# spbka.net
KiCad netlist of a schematic drawn in EAGLE
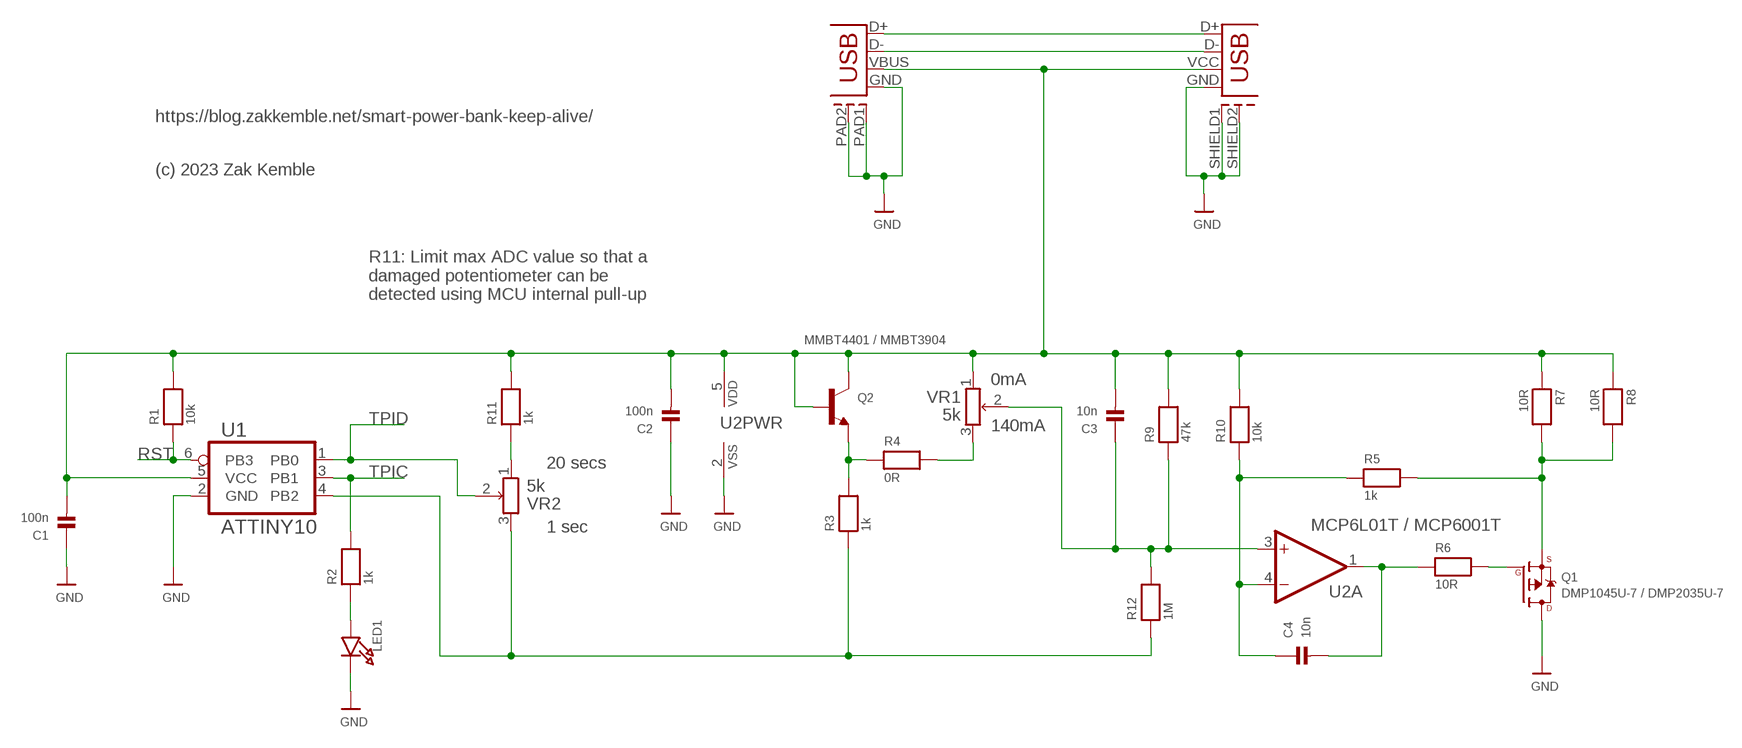
[diagram p0: schematic, sheet 1]

(export (version "E")
  (design (tool "Eeschema 10.0.6"))
  (components
    (comp (ref "C1")
      (value "100n")
      (footprint "eagle-import:0402_XSMALL")
      (libsource (lib "eagle-import") (part "CAP_CERAMIC0402_XSMALL"))
    )
    (comp (ref "C2")
      (value "100n")
      (footprint "eagle-import:0402_XSMALL")
      (libsource (lib "eagle-import") (part "CAP_CERAMIC0402_XSMALL"))
    )
    (comp (ref "C3")
      (value "10n")
      (footprint "eagle-import:0402_XSMALL")
      (libsource (lib "eagle-import") (part "CAP_CERAMIC0402_XSMALL"))
    )
    (comp (ref "C4")
      (value "10n")
      (footprint "eagle-import:0402_XSMALL")
      (libsource (lib "eagle-import") (part "CAP_CERAMIC0402_XSMALL"))
    )
    (comp (ref "LED1")
      (value "LED0603_NOOUTLINE")
      (footprint "eagle-import:CHIPLED_0603_NOOUTLINE")
      (libsource (lib "eagle-import") (part "LED0603_NOOUTLINE"))
    )
    (comp (ref "Q1")
      (value "DMP1045U-7 / DMP2035U-7")
      (footprint "eagle-import:SOT-23-WIDE")
      (libsource (lib "eagle-import") (part "MOSFET-PSOT-23-WIDE"))
    )
    (comp (ref "Q2")
      (value "MMBT4401 / MMBT3904")
      (footprint "eagle-import:SOT23-R")
      (libsource (lib "eagle-import") (part "TRANSISTOR_NPN"))
    )
    (comp (ref "R1")
      (value "10k")
      (footprint "eagle-import:0402_XSMALL")
      (libsource (lib "eagle-import") (part "RESISTOR0402_XSMALL"))
    )
    (comp (ref "R2")
      (value "1k")
      (footprint "eagle-import:0402_XSMALL")
      (libsource (lib "eagle-import") (part "RESISTOR0402_XSMALL"))
    )
    (comp (ref "R3")
      (value "1k")
      (footprint "eagle-import:0402_XSMALL")
      (libsource (lib "eagle-import") (part "RESISTOR0402_XSMALL"))
    )
    (comp (ref "R4")
      (value "0R")
      (footprint "eagle-import:0402_XSMALL")
      (libsource (lib "eagle-import") (part "RESISTOR0402_XSMALL"))
    )
    (comp (ref "R5")
      (value "1k")
      (footprint "eagle-import:0402_XSMALL")
      (libsource (lib "eagle-import") (part "RESISTOR0402_XSMALL"))
    )
    (comp (ref "R6")
      (value "10R")
      (footprint "eagle-import:0402_XSMALL")
      (libsource (lib "eagle-import") (part "RESISTOR0402_XSMALL"))
    )
    (comp (ref "R7")
      (value "10R")
      (footprint "eagle-import:0402_XSMALL")
      (libsource (lib "eagle-import") (part "RESISTOR0402_XSMALL"))
    )
    (comp (ref "R8")
      (value "10R")
      (footprint "eagle-import:0402_XSMALL")
      (libsource (lib "eagle-import") (part "RESISTOR0402_XSMALL"))
    )
    (comp (ref "R9")
      (value "47k")
      (footprint "eagle-import:0402_XSMALL")
      (libsource (lib "eagle-import") (part "RESISTOR0402_XSMALL"))
    )
    (comp (ref "R10")
      (value "10k")
      (footprint "eagle-import:0402_XSMALL")
      (libsource (lib "eagle-import") (part "RESISTOR0402_XSMALL"))
    )
    (comp (ref "R11")
      (value "1k")
      (footprint "eagle-import:0402_XSMALL")
      (libsource (lib "eagle-import") (part "RESISTOR0402_XSMALL"))
    )
    (comp (ref "R12")
      (value "1M")
      (footprint "eagle-import:0402_XSMALL")
      (libsource (lib "eagle-import") (part "RESISTOR0402_XSMALL"))
    )
    (comp (ref "U1")
      (value "ATTINY10")
      (footprint "eagle-import:SOT23-6_SM_PAD")
      (libsource (lib "eagle-import") (part "ATTINY10SM_PAD"))
    )
    (comp (ref "U2")
      (value "MCP6L01T / MCP6001T")
      (footprint "eagle-import:SOT23-5_SM_PAD")
      (libsource (lib "eagle-import") (part "OPAMP_SINGLECONFIG1_SMPAD"))
    )
    (comp (ref "USB1")
      (value "USB-TYPE-AHORZ")
      (footprint "eagle-import:USB-TYPE-A")
      (libsource (lib "eagle-import") (part "USB-TYPE-AHORZ"))
    )
    (comp (ref "USB2")
      (value "USB-PLUG")
      (footprint "eagle-import:USB-TYPE-A-PLUG-SLOT")
      (libsource (lib "eagle-import") (part "USB-PLUG"))
    )
    (comp (ref "VR1")
      (value "5k")
      (footprint "eagle-import:TRIMPOT_BOURNS3MM")
      (libsource (lib "eagle-import") (part "POTENTIOMETERBOURNS3MM"))
    )
    (comp (ref "VR2")
      (value "5k")
      (footprint "eagle-import:TRIMPOT_BOURNS3MM")
      (libsource (lib "eagle-import") (part "POTENTIOMETERBOURNS3MM"))
    )
  )
  (nets
    (net (code "1") (name "/RST") (class "Default")
      (node (ref "R1") (pin "1") (pinfunction "1_1") (pintype "passive"))
      (node (ref "U1") (pin "6") (pinfunction "PB3_6") (pintype "bidirectional"))
    )
    (net (code "2") (name "/TPIC") (class "Default")
      (node (ref "R2") (pin "2") (pinfunction "2_2") (pintype "passive"))
      (node (ref "U1") (pin "3") (pinfunction "PB1_3") (pintype "bidirectional"))
    )
    (net (code "3") (name "/TPID") (class "Default")
      (node (ref "U1") (pin "1") (pinfunction "PB0_1") (pintype "bidirectional"))
      (node (ref "VR2") (pin "2") (pinfunction "1S_2") (pintype "passive"))
    )
    (net (code "4") (name "GND") (class "Default")
      (node (ref "C1") (pin "1") (pinfunction "P$1_1") (pintype "passive"))
      (node (ref "C2") (pin "1") (pinfunction "P$1_1") (pintype "passive"))
      (node (ref "LED1") (pin "C") (pinfunction "C_C") (pintype "passive"))
      (node (ref "Q1") (pin "3") (pinfunction "D_3") (pintype "passive"))
      (node (ref "U1") (pin "2") (pinfunction "GND_2") (pintype "passive"))
      (node (ref "U2") (pin "2") (pinfunction "VSS_2") (pintype "power_in"))
      (node (ref "USB1") (pin "GND") (pinfunction "GND_GND") (pintype "bidirectional"))
      (node (ref "USB1") (pin "SHIELD1") (pinfunction "SHEILD1_SHIELD1") (pintype "bidirectional"))
      (node (ref "USB1") (pin "SHIELD2") (pinfunction "SHEILD2_SHIELD2") (pintype "bidirectional"))
      (node (ref "USB2") (pin "GND") (pinfunction "GND_GND") (pintype "bidirectional"))
      (node (ref "USB2") (pin "PAD1") (pinfunction "SHEILD1_PAD1") (pintype "bidirectional"))
      (node (ref "USB2") (pin "PAD2") (pinfunction "SHEILD2_PAD2") (pintype "bidirectional"))
    )
    (net (code "5") (name "Net-(C1-P$2)") (class "Default")
      (node (ref "C1") (pin "2") (pinfunction "P$2_2") (pintype "passive"))
      (node (ref "C2") (pin "2") (pinfunction "P$2_2") (pintype "passive"))
      (node (ref "C3") (pin "2") (pinfunction "P$2_2") (pintype "passive"))
      (node (ref "Q2") (pin "1") (pinfunction "B_1") (pintype "passive"))
      (node (ref "Q2") (pin "3") (pinfunction "C_3") (pintype "passive"))
      (node (ref "R1") (pin "2") (pinfunction "2_2") (pintype "passive"))
      (node (ref "R10") (pin "2") (pinfunction "2_2") (pintype "passive"))
      (node (ref "R11") (pin "2") (pinfunction "2_2") (pintype "passive"))
      (node (ref "R7") (pin "1") (pinfunction "1_1") (pintype "passive"))
      (node (ref "R8") (pin "1") (pinfunction "1_1") (pintype "passive"))
      (node (ref "R9") (pin "2") (pinfunction "2_2") (pintype "passive"))
      (node (ref "U1") (pin "5") (pinfunction "VCC_5") (pintype "power_in"))
      (node (ref "U2") (pin "5") (pinfunction "VDD_5") (pintype "power_in"))
      (node (ref "USB1") (pin "VCC") (pinfunction "VBUS_VCC") (pintype "bidirectional"))
      (node (ref "USB2") (pin "VBUS") (pinfunction "VBUS_VBUS") (pintype "bidirectional"))
      (node (ref "VR1") (pin "1") (pinfunction "1A_1") (pintype "passive"))
    )
    (net (code "6") (name "Net-(C3-P$1)") (class "Default")
      (node (ref "C3") (pin "1") (pinfunction "P$1_1") (pintype "passive"))
      (node (ref "R12") (pin "2") (pinfunction "2_2") (pintype "passive"))
      (node (ref "R9") (pin "1") (pinfunction "1_1") (pintype "passive"))
      (node (ref "U2") (pin "3") (pinfunction "+IN_3") (pintype "input"))
      (node (ref "VR1") (pin "2") (pinfunction "1S_2") (pintype "passive"))
    )
    (net (code "7") (name "Net-(C4-P$1)") (class "Default")
      (node (ref "C4") (pin "1") (pinfunction "P$1_1") (pintype "passive"))
      (node (ref "R10") (pin "1") (pinfunction "1_1") (pintype "passive"))
      (node (ref "R5") (pin "1") (pinfunction "1_1") (pintype "passive"))
      (node (ref "U2") (pin "4") (pinfunction "-IN_4") (pintype "input"))
    )
    (net (code "8") (name "Net-(C4-P$2)") (class "Default")
      (node (ref "C4") (pin "2") (pinfunction "P$2_2") (pintype "passive"))
      (node (ref "R6") (pin "1") (pinfunction "1_1") (pintype "passive"))
      (node (ref "U2") (pin "1") (pinfunction "OUT_1") (pintype "output"))
    )
    (net (code "9") (name "Net-(LED1-PadA)") (class "Default")
      (node (ref "LED1") (pin "A") (pinfunction "A_A") (pintype "passive"))
      (node (ref "R2") (pin "1") (pinfunction "1_1") (pintype "passive"))
    )
    (net (code "10") (name "Net-(Q1-G)") (class "Default")
      (node (ref "Q1") (pin "1") (pinfunction "G_1") (pintype "passive"))
      (node (ref "R6") (pin "2") (pinfunction "2_2") (pintype "passive"))
    )
    (net (code "11") (name "Net-(Q1-S)") (class "Default")
      (node (ref "Q1") (pin "2") (pinfunction "S_2") (pintype "passive"))
      (node (ref "R5") (pin "2") (pinfunction "2_2") (pintype "passive"))
      (node (ref "R7") (pin "2") (pinfunction "2_2") (pintype "passive"))
      (node (ref "R8") (pin "2") (pinfunction "2_2") (pintype "passive"))
    )
    (net (code "12") (name "Net-(Q2-E)") (class "Default")
      (node (ref "Q2") (pin "2") (pinfunction "E_2") (pintype "passive"))
      (node (ref "R3") (pin "2") (pinfunction "2_2") (pintype "passive"))
      (node (ref "R4") (pin "1") (pinfunction "1_1") (pintype "passive"))
    )
    (net (code "13") (name "Net-(U1-PB2)") (class "Default")
      (node (ref "R12") (pin "1") (pinfunction "1_1") (pintype "passive"))
      (node (ref "R3") (pin "1") (pinfunction "1_1") (pintype "passive"))
      (node (ref "U1") (pin "4") (pinfunction "PB2_4") (pintype "bidirectional"))
      (node (ref "VR2") (pin "3") (pinfunction "1E_3") (pintype "passive"))
    )
    (net (code "14") (name "Net-(USB1-PadD+)") (class "Default")
      (node (ref "USB1") (pin "D+") (pinfunction "D+_D+") (pintype "bidirectional"))
      (node (ref "USB2") (pin "D+") (pinfunction "D+_D+") (pintype "bidirectional"))
    )
    (net (code "15") (name "Net-(USB1-PadD-)") (class "Default")
      (node (ref "USB1") (pin "D-") (pinfunction "D-_D-") (pintype "bidirectional"))
      (node (ref "USB2") (pin "D-") (pinfunction "D-_D-") (pintype "bidirectional"))
    )
    (net (code "16") (name "Net-(VR1-1E)") (class "Default")
      (node (ref "R4") (pin "2") (pinfunction "2_2") (pintype "passive"))
      (node (ref "VR1") (pin "3") (pinfunction "1E_3") (pintype "passive"))
    )
    (net (code "17") (name "Net-(VR2-1A)") (class "Default")
      (node (ref "R11") (pin "1") (pinfunction "1_1") (pintype "passive"))
      (node (ref "VR2") (pin "1") (pinfunction "1A_1") (pintype "passive"))
    )
  )
)
